# STM32F407VGT6.net
KiCad netlist of a schematic drawn in Altium Designer
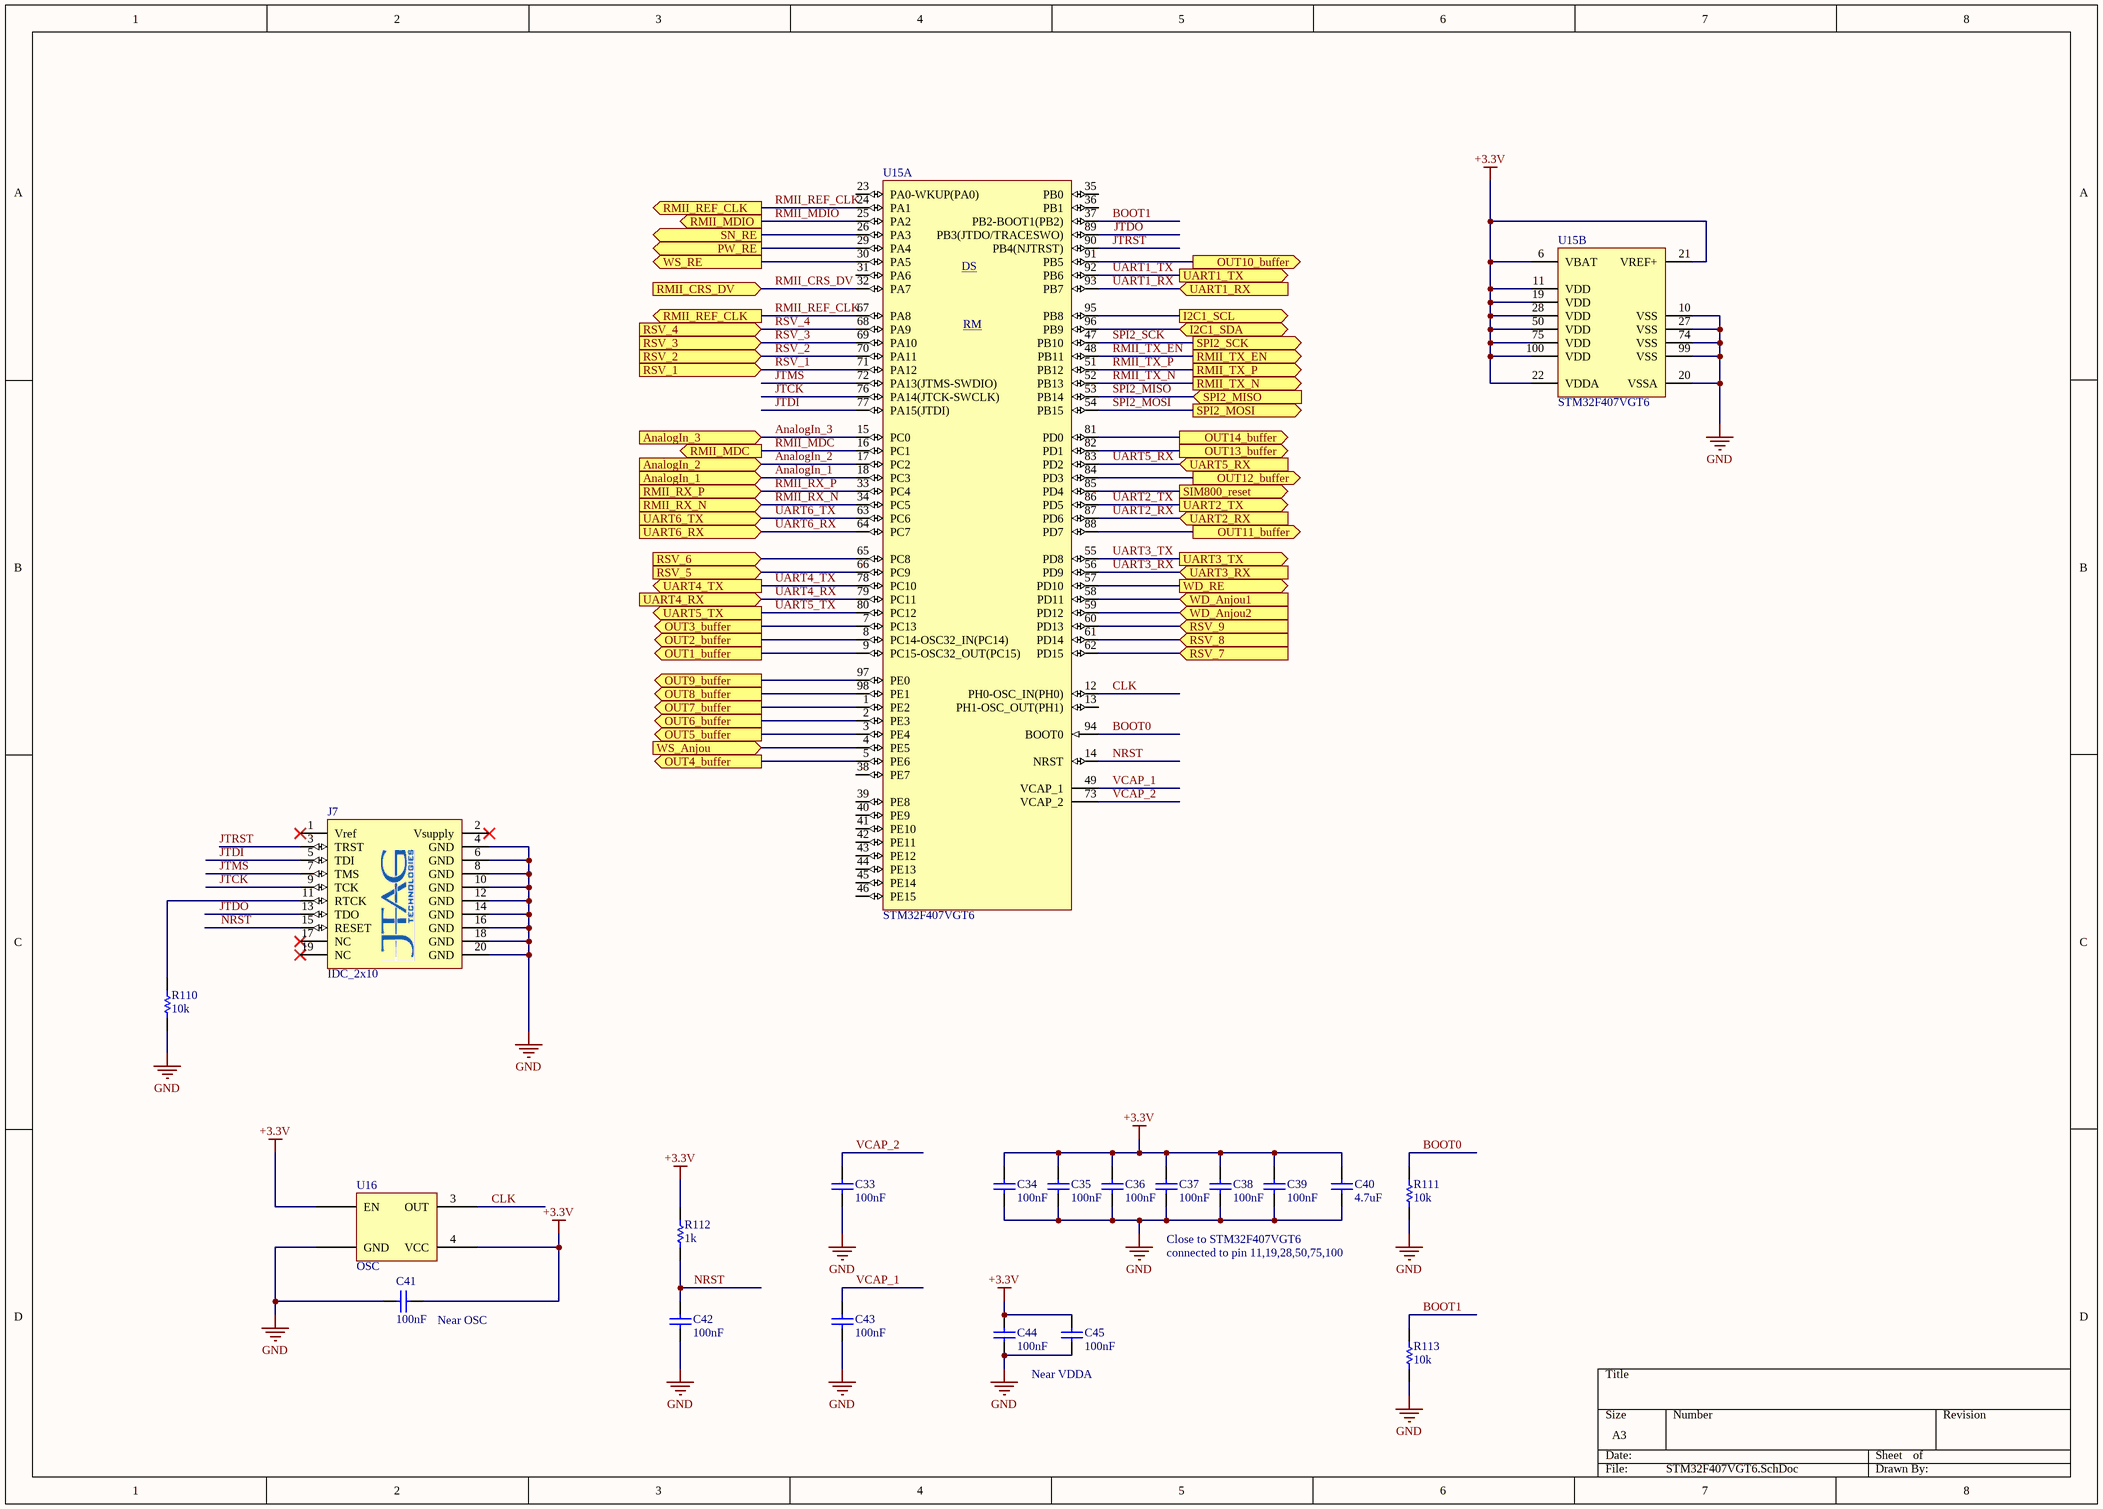
[diagram p0: STM32F407VGT6.SchDoc]

(export (version "E")
  (design (tool "Eeschema 10.0.6"))
  (components
    (comp (ref "C33")
      (value "100nF")
      (footprint "C-805")
      (description "Capacitor")
      (fields (field (name "Comment") "C-805") (field (name "PUBLISHER") "Altium Limited"))
      (libsource (lib "AfraLIB") (part "C-805"))
    )
    (comp (ref "C34")
      (value "100nF")
      (footprint "C-805")
      (description "Capacitor")
      (fields (field (name "Comment") "C-805") (field (name "PUBLISHER") "Altium Limited"))
      (libsource (lib "AfraLIB") (part "C-805"))
    )
    (comp (ref "C35")
      (value "100nF")
      (footprint "C-805")
      (description "Capacitor")
      (fields (field (name "Comment") "C-805") (field (name "PUBLISHER") "Altium Limited"))
      (libsource (lib "AfraLIB") (part "C-805"))
    )
    (comp (ref "C36")
      (value "100nF")
      (footprint "C-805")
      (description "Capacitor")
      (fields (field (name "Comment") "C-805") (field (name "PUBLISHER") "Altium Limited"))
      (libsource (lib "AfraLIB") (part "C-805"))
    )
    (comp (ref "C37")
      (value "100nF")
      (footprint "C-805")
      (description "Capacitor")
      (fields (field (name "Comment") "C-805") (field (name "PUBLISHER") "Altium Limited"))
      (libsource (lib "AfraLIB") (part "C-805"))
    )
    (comp (ref "C38")
      (value "100nF")
      (footprint "C-805")
      (description "Capacitor")
      (fields (field (name "Comment") "C-805") (field (name "PUBLISHER") "Altium Limited"))
      (libsource (lib "AfraLIB") (part "C-805"))
    )
    (comp (ref "C39")
      (value "100nF")
      (footprint "C-805")
      (description "Capacitor")
      (fields (field (name "Comment") "C-805") (field (name "PUBLISHER") "Altium Limited"))
      (libsource (lib "AfraLIB") (part "C-805"))
    )
    (comp (ref "C40")
      (value "4.7uF")
      (footprint "C-1206")
      (description "Capacitor")
      (fields (field (name "Comment") "C-1206") (field (name "PUBLISHER") "Altium Limited"))
      (libsource (lib "AfraLIB") (part "C-1206"))
    )
    (comp (ref "C41")
      (value "100nF")
      (footprint "C-805")
      (description "Capacitor")
      (fields (field (name "Comment") "C-805") (field (name "PUBLISHER") "Altium Limited"))
      (libsource (lib "AfraLIB") (part "C-805"))
    )
    (comp (ref "C42")
      (value "100nF")
      (footprint "C-805")
      (description "Capacitor")
      (fields (field (name "Comment") "C-805") (field (name "PUBLISHER") "Altium Limited"))
      (libsource (lib "AfraLIB") (part "C-805"))
    )
    (comp (ref "C43")
      (value "100nF")
      (footprint "C-805")
      (description "Capacitor")
      (fields (field (name "Comment") "C-805") (field (name "PUBLISHER") "Altium Limited"))
      (libsource (lib "AfraLIB") (part "C-805"))
    )
    (comp (ref "C44")
      (value "100nF")
      (footprint "C-805")
      (description "Capacitor")
      (fields (field (name "Comment") "C-805") (field (name "PUBLISHER") "Altium Limited"))
      (libsource (lib "AfraLIB") (part "C-805"))
    )
    (comp (ref "C45")
      (value "100nF")
      (footprint "C-805")
      (description "Capacitor")
      (fields (field (name "Comment") "C-805") (field (name "PUBLISHER") "Altium Limited"))
      (libsource (lib "AfraLIB") (part "C-805"))
    )
    (comp (ref "J7")
      (value "IDC_2x10")
      (footprint "IDC2.54-V20D")
      (description "20 Pin Standard JTAG Header For ARM JLINK")
      (fields (field (name "DESIGNER") "Eng. Saeid Jorablo") (field (name "PUBLISHER") "SJ UnLimited"))
      (libsource (lib "AfraLIB") (part "JTAG_JLINK"))
    )
    (comp (ref "R110")
      (value "10k")
      (footprint "R-805")
      (description "Resistor")
      (fields (field (name "Comment") "R-805"))
      (libsource (lib "AfraLIB") (part "R-805"))
    )
    (comp (ref "R111")
      (value "10k")
      (footprint "R-805")
      (description "Resistor")
      (fields (field (name "Comment") "R-805"))
      (libsource (lib "AfraLIB") (part "R-805"))
    )
    (comp (ref "R112")
      (value "1k")
      (footprint "R-805")
      (description "Resistor")
      (fields (field (name "Comment") "R-805"))
      (libsource (lib "AfraLIB") (part "R-805"))
    )
    (comp (ref "R113")
      (value "10k")
      (footprint "R-805")
      (description "Resistor")
      (fields (field (name "Comment") "R-805"))
      (libsource (lib "AfraLIB") (part "R-805"))
    )
    (comp (ref "U15")
      (value "STM32F407VGT6")
      (footprint "STM-LQFP100_N")
      (fields (field (name "MANUFACTURER") "STMicroelectronics"))
      (libsource (lib "AfraLIB") (part "STM32F407VGT6"))
    )
    (comp (ref "U16") (value "OSC") (footprint "OSC") (libsource (lib "AfraLIB") (part "OSC")))
  )
  (nets
    (net (code "1") (name "+3.3V") (class "Default")
      (node (ref "C34") (pin "1") (pinfunction "1_1") (pintype "passive"))
      (node (ref "C35") (pin "1") (pinfunction "1_1") (pintype "passive"))
      (node (ref "C36") (pin "1") (pinfunction "1_1") (pintype "passive"))
      (node (ref "C37") (pin "1") (pinfunction "1_1") (pintype "passive"))
      (node (ref "C38") (pin "1") (pinfunction "1_1") (pintype "passive"))
      (node (ref "C39") (pin "1") (pinfunction "1_1") (pintype "passive"))
      (node (ref "C40") (pin "2") (pinfunction "2_2") (pintype "passive"))
      (node (ref "C41") (pin "1") (pinfunction "1_1") (pintype "passive"))
      (node (ref "C44") (pin "1") (pinfunction "1_1") (pintype "passive"))
      (node (ref "C45") (pin "1") (pinfunction "1_1") (pintype "passive"))
      (node (ref "R112") (pin "1") (pinfunction "1_1") (pintype "passive"))
      (node (ref "U15") (pin "100") (pinfunction "VDD_100") (pintype "power_in"))
      (node (ref "U15") (pin "11") (pinfunction "VDD_11") (pintype "power_in"))
      (node (ref "U15") (pin "19") (pinfunction "VDD_19") (pintype "power_in"))
      (node (ref "U15") (pin "21") (pinfunction "VREF+_21") (pintype "power_in"))
      (node (ref "U15") (pin "22") (pinfunction "VDDA_22") (pintype "power_in"))
      (node (ref "U15") (pin "28") (pinfunction "VDD_28") (pintype "power_in"))
      (node (ref "U15") (pin "50") (pinfunction "VDD_50") (pintype "power_in"))
      (node (ref "U15") (pin "6") (pinfunction "VBAT_6") (pintype "power_in"))
      (node (ref "U15") (pin "75") (pinfunction "VDD_75") (pintype "power_in"))
      (node (ref "U16") (pin "1") (pinfunction "EN_1") (pintype "passive"))
      (node (ref "U16") (pin "4") (pinfunction "VCC_4") (pintype "passive"))
    )
    (net (code "2") (name "/AnalogIn_1") (class "Default")
      (node (ref "U15") (pin "18") (pinfunction "PC3_18") (pintype "bidirectional"))
    )
    (net (code "3") (name "/AnalogIn_2") (class "Default")
      (node (ref "U15") (pin "17") (pinfunction "PC2_17") (pintype "bidirectional"))
    )
    (net (code "4") (name "/AnalogIn_3") (class "Default")
      (node (ref "U15") (pin "15") (pinfunction "PC0_15") (pintype "bidirectional"))
    )
    (net (code "5") (name "/BOOT0") (class "Default")
      (node (ref "R111") (pin "1") (pinfunction "1_1") (pintype "passive"))
      (node (ref "U15") (pin "94") (pinfunction "BOOT0_94") (pintype "input"))
    )
    (net (code "6") (name "/BOOT1") (class "Default")
      (node (ref "R113") (pin "1") (pinfunction "1_1") (pintype "passive"))
      (node (ref "U15") (pin "37") (pinfunction "PB2-BOOT1(PB2)_37") (pintype "bidirectional"))
    )
    (net (code "7") (name "/CLK") (class "Default")
      (node (ref "U15") (pin "12") (pinfunction "PH0-OSC_IN(PH0)_12") (pintype "bidirectional"))
      (node (ref "U16") (pin "3") (pinfunction "OUT_3") (pintype "passive"))
    )
    (net (code "8") (name "/I2C1_SCL") (class "Default")
      (node (ref "U15") (pin "95") (pinfunction "PB8_95") (pintype "bidirectional"))
    )
    (net (code "9") (name "/I2C1_SDA") (class "Default")
      (node (ref "U15") (pin "96") (pinfunction "PB9_96") (pintype "bidirectional"))
    )
    (net (code "10") (name "/JTCK") (class "Default")
      (node (ref "J7") (pin "9") (pinfunction "TCK_9") (pintype "bidirectional"))
      (node (ref "U15") (pin "76") (pinfunction "PA14(JTCK-SWCLK)_76") (pintype "bidirectional"))
    )
    (net (code "11") (name "/JTDI") (class "Default")
      (node (ref "J7") (pin "5") (pinfunction "TDI_5") (pintype "bidirectional"))
      (node (ref "U15") (pin "77") (pinfunction "PA15(JTDI)_77") (pintype "bidirectional"))
    )
    (net (code "12") (name "/JTDO") (class "Default")
      (node (ref "J7") (pin "13") (pinfunction "TDO_13") (pintype "bidirectional"))
      (node (ref "U15") (pin "89") (pinfunction "PB3(JTDO/TRACESWO)_89") (pintype "bidirectional"))
    )
    (net (code "13") (name "/JTMS") (class "Default")
      (node (ref "J7") (pin "7") (pinfunction "TMS_7") (pintype "bidirectional"))
      (node (ref "U15") (pin "72") (pinfunction "PA13(JTMS-SWDIO)_72") (pintype "bidirectional"))
    )
    (net (code "14") (name "/JTRST") (class "Default")
      (node (ref "J7") (pin "3") (pinfunction "TRST_3") (pintype "bidirectional"))
      (node (ref "U15") (pin "90") (pinfunction "PB4(NJTRST)_90") (pintype "bidirectional"))
    )
    (net (code "15") (name "/NRST") (class "Default")
      (node (ref "C42") (pin "1") (pinfunction "1_1") (pintype "passive"))
      (node (ref "J7") (pin "15") (pinfunction "RESET_15") (pintype "bidirectional"))
      (node (ref "R112") (pin "2") (pinfunction "2_2") (pintype "passive"))
      (node (ref "U15") (pin "14") (pinfunction "NRST_14") (pintype "bidirectional"))
    )
    (net (code "16") (name "/OUT1_buffer") (class "Default")
      (node (ref "U15") (pin "9") (pinfunction "PC15-OSC32_OUT(PC15)_9") (pintype "bidirectional"))
    )
    (net (code "17") (name "/OUT2_buffer") (class "Default")
      (node (ref "U15") (pin "8") (pinfunction "PC14-OSC32_IN(PC14)_8") (pintype "bidirectional"))
    )
    (net (code "18") (name "/OUT3_buffer") (class "Default")
      (node (ref "U15") (pin "7") (pinfunction "PC13_7") (pintype "bidirectional"))
    )
    (net (code "19") (name "/OUT4_buffer") (class "Default")
      (node (ref "U15") (pin "5") (pinfunction "PE6_5") (pintype "bidirectional"))
    )
    (net (code "20") (name "/OUT5_buffer") (class "Default")
      (node (ref "U15") (pin "3") (pinfunction "PE4_3") (pintype "bidirectional"))
    )
    (net (code "21") (name "/OUT6_buffer") (class "Default")
      (node (ref "U15") (pin "2") (pinfunction "PE3_2") (pintype "bidirectional"))
    )
    (net (code "22") (name "/OUT7_buffer") (class "Default")
      (node (ref "U15") (pin "1") (pinfunction "PE2_1") (pintype "bidirectional"))
    )
    (net (code "23") (name "/OUT8_buffer") (class "Default")
      (node (ref "U15") (pin "98") (pinfunction "PE1_98") (pintype "bidirectional"))
    )
    (net (code "24") (name "/OUT9_buffer") (class "Default")
      (node (ref "U15") (pin "97") (pinfunction "PE0_97") (pintype "bidirectional"))
    )
    (net (code "25") (name "/OUT10_buffer") (class "Default")
      (node (ref "U15") (pin "91") (pinfunction "PB5_91") (pintype "bidirectional"))
    )
    (net (code "26") (name "/OUT11_buffer") (class "Default")
      (node (ref "U15") (pin "88") (pinfunction "PD7_88") (pintype "bidirectional"))
    )
    (net (code "27") (name "/OUT12_buffer") (class "Default")
      (node (ref "U15") (pin "84") (pinfunction "PD3_84") (pintype "bidirectional"))
    )
    (net (code "28") (name "/OUT13_buffer") (class "Default")
      (node (ref "U15") (pin "82") (pinfunction "PD1_82") (pintype "bidirectional"))
    )
    (net (code "29") (name "/OUT14_buffer") (class "Default")
      (node (ref "U15") (pin "81") (pinfunction "PD0_81") (pintype "bidirectional"))
    )
    (net (code "30") (name "/PW_RE") (class "Default")
      (node (ref "U15") (pin "29") (pinfunction "PA4_29") (pintype "bidirectional"))
    )
    (net (code "31") (name "/RMII_CRS_DV") (class "Default")
      (node (ref "U15") (pin "32") (pinfunction "PA7_32") (pintype "bidirectional"))
    )
    (net (code "32") (name "/RMII_MDC") (class "Default")
      (node (ref "U15") (pin "16") (pinfunction "PC1_16") (pintype "bidirectional"))
    )
    (net (code "33") (name "/RMII_MDIO") (class "Default")
      (node (ref "U15") (pin "25") (pinfunction "PA2_25") (pintype "bidirectional"))
    )
    (net (code "34") (name "/RMII_REF_CLK") (class "Default")
      (node (ref "U15") (pin "24") (pinfunction "PA1_24") (pintype "bidirectional"))
      (node (ref "U15") (pin "67") (pinfunction "PA8_67") (pintype "bidirectional"))
    )
    (net (code "35") (name "/RMII_RX_N") (class "Default")
      (node (ref "U15") (pin "34") (pinfunction "PC5_34") (pintype "bidirectional"))
    )
    (net (code "36") (name "/RMII_RX_P") (class "Default")
      (node (ref "U15") (pin "33") (pinfunction "PC4_33") (pintype "bidirectional"))
    )
    (net (code "37") (name "/RMII_TX_EN") (class "Default")
      (node (ref "U15") (pin "48") (pinfunction "PB11_48") (pintype "bidirectional"))
    )
    (net (code "38") (name "/RMII_TX_N") (class "Default")
      (node (ref "U15") (pin "52") (pinfunction "PB13_52") (pintype "bidirectional"))
    )
    (net (code "39") (name "/RMII_TX_P") (class "Default")
      (node (ref "U15") (pin "51") (pinfunction "PB12_51") (pintype "bidirectional"))
    )
    (net (code "40") (name "/RSV_1") (class "Default")
      (node (ref "U15") (pin "71") (pinfunction "PA12_71") (pintype "bidirectional"))
    )
    (net (code "41") (name "/RSV_2") (class "Default")
      (node (ref "U15") (pin "70") (pinfunction "PA11_70") (pintype "bidirectional"))
    )
    (net (code "42") (name "/RSV_3") (class "Default")
      (node (ref "U15") (pin "69") (pinfunction "PA10_69") (pintype "bidirectional"))
    )
    (net (code "43") (name "/RSV_4") (class "Default")
      (node (ref "U15") (pin "68") (pinfunction "PA9_68") (pintype "bidirectional"))
    )
    (net (code "44") (name "/RSV_5") (class "Default")
      (node (ref "U15") (pin "66") (pinfunction "PC9_66") (pintype "bidirectional"))
    )
    (net (code "45") (name "/RSV_6") (class "Default")
      (node (ref "U15") (pin "65") (pinfunction "PC8_65") (pintype "bidirectional"))
    )
    (net (code "46") (name "/RSV_7") (class "Default")
      (node (ref "U15") (pin "62") (pinfunction "PD15_62") (pintype "bidirectional"))
    )
    (net (code "47") (name "/RSV_8") (class "Default")
      (node (ref "U15") (pin "61") (pinfunction "PD14_61") (pintype "bidirectional"))
    )
    (net (code "48") (name "/RSV_9") (class "Default")
      (node (ref "U15") (pin "60") (pinfunction "PD13_60") (pintype "bidirectional"))
    )
    (net (code "49") (name "/SIM800_reset") (class "Default")
      (node (ref "U15") (pin "85") (pinfunction "PD4_85") (pintype "bidirectional"))
    )
    (net (code "50") (name "/SN_RE") (class "Default")
      (node (ref "U15") (pin "26") (pinfunction "PA3_26") (pintype "bidirectional"))
    )
    (net (code "51") (name "/SPI2_MISO") (class "Default")
      (node (ref "U15") (pin "53") (pinfunction "PB14_53") (pintype "bidirectional"))
    )
    (net (code "52") (name "/SPI2_MOSI") (class "Default")
      (node (ref "U15") (pin "54") (pinfunction "PB15_54") (pintype "bidirectional"))
    )
    (net (code "53") (name "/SPI2_SCK") (class "Default")
      (node (ref "U15") (pin "47") (pinfunction "PB10_47") (pintype "bidirectional"))
    )
    (net (code "54") (name "/UART1_RX") (class "Default")
      (node (ref "U15") (pin "93") (pinfunction "PB7_93") (pintype "bidirectional"))
    )
    (net (code "55") (name "/UART1_TX") (class "Default")
      (node (ref "U15") (pin "92") (pinfunction "PB6_92") (pintype "bidirectional"))
    )
    (net (code "56") (name "/UART2_RX") (class "Default")
      (node (ref "U15") (pin "87") (pinfunction "PD6_87") (pintype "bidirectional"))
    )
    (net (code "57") (name "/UART2_TX") (class "Default")
      (node (ref "U15") (pin "86") (pinfunction "PD5_86") (pintype "bidirectional"))
    )
    (net (code "58") (name "/UART3_RX") (class "Default")
      (node (ref "U15") (pin "56") (pinfunction "PD9_56") (pintype "bidirectional"))
    )
    (net (code "59") (name "/UART3_TX") (class "Default")
      (node (ref "U15") (pin "55") (pinfunction "PD8_55") (pintype "bidirectional"))
    )
    (net (code "60") (name "/UART4_RX") (class "Default")
      (node (ref "U15") (pin "79") (pinfunction "PC11_79") (pintype "bidirectional"))
    )
    (net (code "61") (name "/UART4_TX") (class "Default")
      (node (ref "U15") (pin "78") (pinfunction "PC10_78") (pintype "bidirectional"))
    )
    (net (code "62") (name "/UART5_RX") (class "Default")
      (node (ref "U15") (pin "83") (pinfunction "PD2_83") (pintype "bidirectional"))
    )
    (net (code "63") (name "/UART5_TX") (class "Default")
      (node (ref "U15") (pin "80") (pinfunction "PC12_80") (pintype "bidirectional"))
    )
    (net (code "64") (name "/UART6_RX") (class "Default")
      (node (ref "U15") (pin "64") (pinfunction "PC7_64") (pintype "bidirectional"))
    )
    (net (code "65") (name "/UART6_TX") (class "Default")
      (node (ref "U15") (pin "63") (pinfunction "PC6_63") (pintype "bidirectional"))
    )
    (net (code "66") (name "/VCAP_1") (class "Default")
      (node (ref "C43") (pin "1") (pinfunction "1_1") (pintype "passive"))
      (node (ref "U15") (pin "49") (pinfunction "VCAP_1_49") (pintype "power_in"))
    )
    (net (code "67") (name "/VCAP_2") (class "Default")
      (node (ref "C33") (pin "1") (pinfunction "1_1") (pintype "passive"))
      (node (ref "U15") (pin "73") (pinfunction "VCAP_2_73") (pintype "power_in"))
    )
    (net (code "68") (name "/WD_Anjou1") (class "Default")
      (node (ref "U15") (pin "58") (pinfunction "PD11_58") (pintype "bidirectional"))
    )
    (net (code "69") (name "/WD_Anjou2") (class "Default")
      (node (ref "U15") (pin "59") (pinfunction "PD12_59") (pintype "bidirectional"))
    )
    (net (code "70") (name "/WD_RE") (class "Default")
      (node (ref "U15") (pin "57") (pinfunction "PD10_57") (pintype "bidirectional"))
    )
    (net (code "71") (name "/WS_Anjou") (class "Default")
      (node (ref "U15") (pin "4") (pinfunction "PE5_4") (pintype "bidirectional"))
    )
    (net (code "72") (name "/WS_RE") (class "Default")
      (node (ref "U15") (pin "30") (pinfunction "PA5_30") (pintype "bidirectional"))
    )
    (net (code "73") (name "GND") (class "Default")
      (node (ref "C33") (pin "2") (pinfunction "2_2") (pintype "passive"))
      (node (ref "C34") (pin "2") (pinfunction "2_2") (pintype "passive"))
      (node (ref "C35") (pin "2") (pinfunction "2_2") (pintype "passive"))
      (node (ref "C36") (pin "2") (pinfunction "2_2") (pintype "passive"))
      (node (ref "C37") (pin "2") (pinfunction "2_2") (pintype "passive"))
      (node (ref "C38") (pin "2") (pinfunction "2_2") (pintype "passive"))
      (node (ref "C39") (pin "2") (pinfunction "2_2") (pintype "passive"))
      (node (ref "C40") (pin "1") (pinfunction "1_1") (pintype "passive"))
      (node (ref "C41") (pin "2") (pinfunction "2_2") (pintype "passive"))
      (node (ref "C42") (pin "2") (pinfunction "2_2") (pintype "passive"))
      (node (ref "C43") (pin "2") (pinfunction "2_2") (pintype "passive"))
      (node (ref "C44") (pin "2") (pinfunction "2_2") (pintype "passive"))
      (node (ref "C45") (pin "2") (pinfunction "2_2") (pintype "passive"))
      (node (ref "J7") (pin "10") (pinfunction "GND_10") (pintype "power_in"))
      (node (ref "J7") (pin "12") (pinfunction "GND_12") (pintype "power_in"))
      (node (ref "J7") (pin "14") (pinfunction "GND_14") (pintype "power_in"))
      (node (ref "J7") (pin "16") (pinfunction "GND_16") (pintype "power_in"))
      (node (ref "J7") (pin "18") (pinfunction "GND_18") (pintype "power_in"))
      (node (ref "J7") (pin "20") (pinfunction "GND_20") (pintype "power_in"))
      (node (ref "J7") (pin "4") (pinfunction "GND_4") (pintype "power_in"))
      (node (ref "J7") (pin "6") (pinfunction "GND_6") (pintype "power_in"))
      (node (ref "J7") (pin "8") (pinfunction "GND_8") (pintype "power_in"))
      (node (ref "R110") (pin "1") (pinfunction "1_1") (pintype "passive"))
      (node (ref "R111") (pin "2") (pinfunction "2_2") (pintype "passive"))
      (node (ref "R113") (pin "2") (pinfunction "2_2") (pintype "passive"))
      (node (ref "U15") (pin "10") (pinfunction "VSS_10") (pintype "power_in"))
      (node (ref "U15") (pin "20") (pinfunction "VSSA_20") (pintype "power_in"))
      (node (ref "U15") (pin "27") (pinfunction "VSS_27") (pintype "power_in"))
      (node (ref "U15") (pin "74") (pinfunction "VSS_74") (pintype "power_in"))
      (node (ref "U15") (pin "99") (pinfunction "VSS_99") (pintype "power_in"))
      (node (ref "U16") (pin "2") (pinfunction "GND_2") (pintype "passive"))
    )
    (net (code "74") (name "Net-(J7-RTCK)") (class "Default")
      (node (ref "J7") (pin "11") (pinfunction "RTCK_11") (pintype "bidirectional"))
      (node (ref "R110") (pin "2") (pinfunction "2_2") (pintype "passive"))
    )
    (net (code "75") (name "unconnected-(J7-NC-Pad17)") (class "Default")
      (node (ref "J7") (pin "17") (pinfunction "NC_17") (pintype "passive+no_connect"))
    )
    (net (code "76") (name "unconnected-(J7-NC-Pad19)") (class "Default")
      (node (ref "J7") (pin "19") (pinfunction "NC_19") (pintype "passive+no_connect"))
    )
    (net (code "77") (name "unconnected-(J7-Vref-Pad1)") (class "Default")
      (node (ref "J7") (pin "1") (pinfunction "Vref_1") (pintype "power_in+no_connect"))
    )
    (net (code "78") (name "unconnected-(J7-Vsupply-Pad2)") (class "Default")
      (node (ref "J7") (pin "2") (pinfunction "Vsupply_2") (pintype "power_in+no_connect"))
    )
    (net (code "79") (name "unconnected-(U15A-PA0-WKUP(PA0)-Pad23)") (class "Default")
      (node (ref "U15") (pin "23") (pinfunction "PA0-WKUP(PA0)_23") (pintype "bidirectional"))
    )
    (net (code "80") (name "unconnected-(U15A-PA6-Pad31)") (class "Default")
      (node (ref "U15") (pin "31") (pinfunction "PA6_31") (pintype "bidirectional"))
    )
    (net (code "81") (name "unconnected-(U15A-PB0-Pad35)") (class "Default")
      (node (ref "U15") (pin "35") (pinfunction "PB0_35") (pintype "bidirectional"))
    )
    (net (code "82") (name "unconnected-(U15A-PB1-Pad36)") (class "Default")
      (node (ref "U15") (pin "36") (pinfunction "PB1_36") (pintype "bidirectional"))
    )
    (net (code "83") (name "unconnected-(U15A-PE7-Pad38)") (class "Default")
      (node (ref "U15") (pin "38") (pinfunction "PE7_38") (pintype "bidirectional"))
    )
    (net (code "84") (name "unconnected-(U15A-PE8-Pad39)") (class "Default")
      (node (ref "U15") (pin "39") (pinfunction "PE8_39") (pintype "bidirectional"))
    )
    (net (code "85") (name "unconnected-(U15A-PE9-Pad40)") (class "Default")
      (node (ref "U15") (pin "40") (pinfunction "PE9_40") (pintype "bidirectional"))
    )
    (net (code "86") (name "unconnected-(U15A-PE10-Pad41)") (class "Default")
      (node (ref "U15") (pin "41") (pinfunction "PE10_41") (pintype "bidirectional"))
    )
    (net (code "87") (name "unconnected-(U15A-PE11-Pad42)") (class "Default")
      (node (ref "U15") (pin "42") (pinfunction "PE11_42") (pintype "bidirectional"))
    )
    (net (code "88") (name "unconnected-(U15A-PE12-Pad43)") (class "Default")
      (node (ref "U15") (pin "43") (pinfunction "PE12_43") (pintype "bidirectional"))
    )
    (net (code "89") (name "unconnected-(U15A-PE13-Pad44)") (class "Default")
      (node (ref "U15") (pin "44") (pinfunction "PE13_44") (pintype "bidirectional"))
    )
    (net (code "90") (name "unconnected-(U15A-PE14-Pad45)") (class "Default")
      (node (ref "U15") (pin "45") (pinfunction "PE14_45") (pintype "bidirectional"))
    )
    (net (code "91") (name "unconnected-(U15A-PE15-Pad46)") (class "Default")
      (node (ref "U15") (pin "46") (pinfunction "PE15_46") (pintype "bidirectional"))
    )
    (net (code "92") (name "unconnected-(U15A-PH1-OSC_OUT(PH1)-Pad13)") (class "Default")
      (node (ref "U15") (pin "13") (pinfunction "PH1-OSC_OUT(PH1)_13") (pintype "bidirectional"))
    )
  )
)
